# ASBB_BNO055.net
KiCad netlist of a schematic drawn in Altium Designer
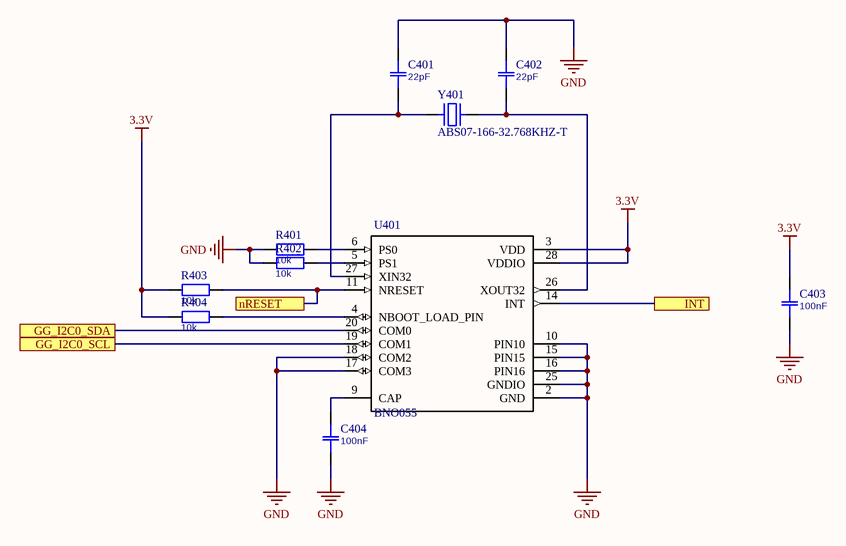
[diagram p0: ASBB_BNO055.SchDoc]

(export (version "E")
  (design (tool "Eeschema 10.0.6"))
  (components
    (comp (ref "C401")
      (value "22pF")
      (footprint "0603")
      (description "Capacitor")
      (fields (field (name "PARTNUMBER") "?"))
      (libsource (lib "FZI") (part "Capacitor"))
    )
    (comp (ref "C402")
      (value "22pF")
      (footprint "0603")
      (description "Capacitor")
      (fields (field (name "PARTNUMBER") "?"))
      (libsource (lib "FZI") (part "Capacitor"))
    )
    (comp (ref "C403")
      (value "100nF")
      (footprint "0603")
      (description "Capacitor")
      (fields (field (name "PARTNUMBER") "?"))
      (libsource (lib "FZI") (part "Capacitor"))
    )
    (comp (ref "C404")
      (value "100nF")
      (footprint "0603")
      (description "Capacitor")
      (fields (field (name "PARTNUMBER") "?"))
      (libsource (lib "FZI") (part "Capacitor"))
    )
    (comp (ref "R401")
      (value "10k")
      (footprint "0603")
      (description "Resistor")
      (fields (field (name "PARTNUMBER") "?"))
      (libsource (lib "FZI") (part "Resistor"))
    )
    (comp (ref "R402")
      (value "10k")
      (footprint "0603")
      (description "Resistor")
      (fields (field (name "PARTNUMBER") "?"))
      (libsource (lib "FZI") (part "Resistor"))
    )
    (comp (ref "R403")
      (value "10k")
      (footprint "0603")
      (description "Resistor")
      (fields (field (name "PARTNUMBER") "?"))
      (libsource (lib "FZI") (part "Resistor"))
    )
    (comp (ref "R404")
      (value "10k")
      (footprint "0603")
      (description "Resistor")
      (fields (field (name "PARTNUMBER") "?"))
      (libsource (lib "FZI") (part "Resistor"))
    )
    (comp (ref "U401")
      (value "BNO055")
      (footprint "LGA28R50P4X10_380X520X100")
      (description "BNO055 9-axis Absolute Orientation Sensor _ SiP _ w/Sensors and Sensor Fusion")
      (fields (field (name "MF") "Bosch"))
      (libsource (lib "BNO055") (part "BNO055"))
    )
    (comp (ref "Y401")
      (value "ABS07-166-32.768KHZ-T")
      (footprint "ABRACON ABS07")
      (description "SMT Crystal")
      (libsource (lib "Crystals") (part "Abracon Crystal ABS06"))
    )
  )
  (nets
    (net (code "1") (name "/GG_I2C0_SCL") (class "Default")
      (node (ref "U401") (pin "19") (pinfunction "COM1_19") (pintype "bidirectional"))
    )
    (net (code "2") (name "/GG_I2C0_SDA") (class "Default")
      (node (ref "U401") (pin "20") (pinfunction "COM0_20") (pintype "bidirectional"))
    )
    (net (code "3") (name "/INT") (class "Default")
      (node (ref "U401") (pin "14") (pinfunction "INT_14") (pintype "output"))
    )
    (net (code "4") (name "/nRESET") (class "Default")
      (node (ref "R403") (pin "2") (pinfunction "2_2") (pintype "passive"))
      (node (ref "U401") (pin "11") (pinfunction "NRESET_11") (pintype "input"))
    )
    (net (code "5") (name "3.3V") (class "Default")
      (node (ref "C403") (pin "2") (pinfunction "2_2") (pintype "passive"))
      (node (ref "R403") (pin "1") (pinfunction "1_1") (pintype "passive"))
      (node (ref "R404") (pin "1") (pinfunction "1_1") (pintype "passive"))
      (node (ref "U401") (pin "28") (pinfunction "VDDIO_28") (pintype "power_in"))
      (node (ref "U401") (pin "3") (pinfunction "VDD_3") (pintype "power_in"))
    )
    (net (code "6") (name "GND") (class "Default")
      (node (ref "C401") (pin "2") (pinfunction "2_2") (pintype "passive"))
      (node (ref "C402") (pin "2") (pinfunction "2_2") (pintype "passive"))
      (node (ref "C403") (pin "1") (pinfunction "1_1") (pintype "passive"))
      (node (ref "C404") (pin "1") (pinfunction "1_1") (pintype "passive"))
      (node (ref "R401") (pin "1") (pinfunction "1_1") (pintype "passive"))
      (node (ref "R402") (pin "1") (pinfunction "1_1") (pintype "passive"))
      (node (ref "U401") (pin "10") (pinfunction "PIN10_10") (pintype "power_in"))
      (node (ref "U401") (pin "15") (pinfunction "PIN15_15") (pintype "power_in"))
      (node (ref "U401") (pin "16") (pinfunction "PIN16_16") (pintype "power_in"))
      (node (ref "U401") (pin "17") (pinfunction "COM3_17") (pintype "bidirectional"))
      (node (ref "U401") (pin "18") (pinfunction "COM2_18") (pintype "bidirectional"))
      (node (ref "U401") (pin "2") (pinfunction "GND_2") (pintype "power_in"))
      (node (ref "U401") (pin "25") (pinfunction "GNDIO_25") (pintype "power_in"))
    )
    (net (code "7") (name "Net-(U401-CAP)") (class "Default")
      (node (ref "C404") (pin "2") (pinfunction "2_2") (pintype "passive"))
      (node (ref "U401") (pin "9") (pinfunction "CAP_9") (pintype "passive"))
    )
    (net (code "8") (name "Net-(U401-NBOOT_LOAD_PIN)") (class "Default")
      (node (ref "R404") (pin "2") (pinfunction "2_2") (pintype "passive"))
      (node (ref "U401") (pin "4") (pinfunction "NBOOT_LOAD_PIN_4") (pintype "bidirectional"))
    )
    (net (code "9") (name "Net-(U401-PS0)") (class "Default")
      (node (ref "R401") (pin "2") (pinfunction "2_2") (pintype "passive"))
      (node (ref "U401") (pin "6") (pinfunction "PS0_6") (pintype "input"))
    )
    (net (code "10") (name "Net-(U401-PS1)") (class "Default")
      (node (ref "R402") (pin "2") (pinfunction "2_2") (pintype "passive"))
      (node (ref "U401") (pin "5") (pinfunction "PS1_5") (pintype "input"))
    )
    (net (code "11") (name "Net-(U401-XIN32)") (class "Default")
      (node (ref "C401") (pin "1") (pinfunction "1_1") (pintype "passive"))
      (node (ref "U401") (pin "27") (pinfunction "XIN32_27") (pintype "input"))
      (node (ref "Y401") (pin "1") (pinfunction "1_1") (pintype "passive"))
    )
    (net (code "12") (name "Net-(U401-XOUT32)") (class "Default")
      (node (ref "C402") (pin "1") (pinfunction "1_1") (pintype "passive"))
      (node (ref "U401") (pin "26") (pinfunction "XOUT32_26") (pintype "output"))
      (node (ref "Y401") (pin "2") (pinfunction "2_2") (pintype "passive"))
    )
  )
)
